# untitled.net
KiCad netlist of a schematic drawn in EAGLE
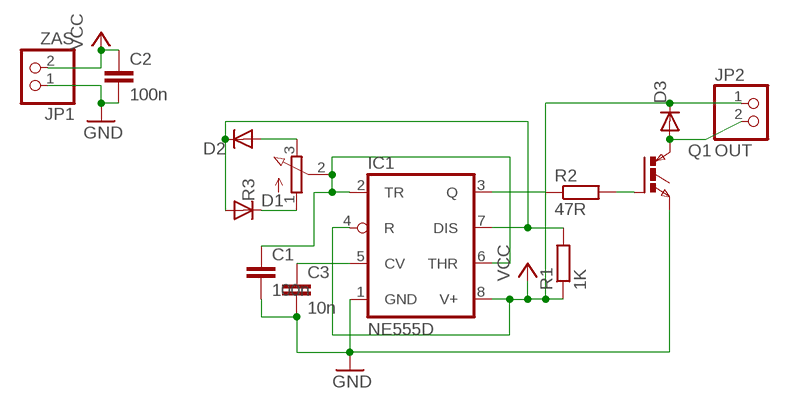
[diagram p0: schematic, sheet 1]

(export (version "E")
  (design (tool "Eeschema 10.0.6"))
  (components
    (comp (ref "C1")
      (value "100n")
      (footprint "eagle-import:C1206")
      (libsource (lib "eagle-import") (part "C-EUC1206"))
    )
    (comp (ref "C2")
      (value "100n")
      (footprint "eagle-import:C1206")
      (libsource (lib "eagle-import") (part "C-EUC1206"))
    )
    (comp (ref "C3")
      (value "10n")
      (footprint "eagle-import:C1206")
      (libsource (lib "eagle-import") (part "C-EUC1206"))
    )
    (comp (ref "D1")
      (value "DIODE-MINIMELF")
      (footprint "eagle-import:MINIMELF")
      (libsource (lib "eagle-import") (part "DIODE-MINIMELF"))
    )
    (comp (ref "D2")
      (value "DIODE-MINIMELF")
      (footprint "eagle-import:MINIMELF")
      (libsource (lib "eagle-import") (part "DIODE-MINIMELF"))
    )
    (comp (ref "D3")
      (value "DIODE-MINIMELF")
      (footprint "eagle-import:MINIMELF")
      (libsource (lib "eagle-import") (part "DIODE-MINIMELF"))
    )
    (comp (ref "IC1")
      (value "NE555D")
      (footprint "eagle-import:SO08")
      (libsource (lib "eagle-import") (part "555DNE"))
    )
    (comp (ref "JP1")
      (value "ZAS")
      (footprint "eagle-import:1X02")
      (libsource (lib "eagle-import") (part "PINHD-1X2"))
    )
    (comp (ref "JP2")
      (value "OUT")
      (footprint "eagle-import:1X02")
      (libsource (lib "eagle-import") (part "PINHD-1X2"))
    )
    (comp (ref "Q1")
      (value "IGBTTO252_STM")
      (footprint "eagle-import:TO252_STM")
      (libsource (lib "eagle-import") (part "IGBTTO252_STM"))
    )
    (comp (ref "R1")
      (value "1K")
      (footprint "eagle-import:R1206")
      (libsource (lib "eagle-import") (part "R-EU_R1206"))
    )
    (comp (ref "R2")
      (value "47R")
      (footprint "eagle-import:R1206")
      (libsource (lib "eagle-import") (part "R-EU_R1206"))
    )
    (comp (ref "R3")
      (value "3RP/1610N")
      (footprint "eagle-import:3RP_1610N")
      (libsource (lib "eagle-import") (part "3RP/1610N"))
    )
  )
  (nets
    (net (code "1") (name "GND") (class "Default")
      (node (ref "C1") (pin "2") (pinfunction "2_2") (pintype "passive"))
      (node (ref "C2") (pin "2") (pinfunction "2_2") (pintype "passive"))
      (node (ref "C3") (pin "2") (pinfunction "2_2") (pintype "passive"))
      (node (ref "IC1") (pin "1") (pinfunction "GND_1") (pintype "power_in"))
      (node (ref "JP1") (pin "1") (pinfunction "1_1") (pintype "passive"))
      (node (ref "Q1") (pin "3") (pinfunction "E_3") (pintype "passive"))
    )
    (net (code "2") (name "Net-(IC1-CV)") (class "Default")
      (node (ref "C3") (pin "1") (pinfunction "1_1") (pintype "passive"))
      (node (ref "IC1") (pin "5") (pinfunction "CV_5") (pintype "input"))
    )
    (net (code "3") (name "Net-(IC1-DIS)") (class "Default")
      (node (ref "D1") (pin "A") (pinfunction "A_A") (pintype "passive"))
      (node (ref "D2") (pin "C") (pinfunction "C_C") (pintype "passive"))
      (node (ref "IC1") (pin "7") (pinfunction "DIS_7") (pintype "input"))
      (node (ref "R1") (pin "2") (pinfunction "2_2") (pintype "passive"))
    )
    (net (code "4") (name "Net-(IC1-Q)") (class "Default")
      (node (ref "IC1") (pin "3") (pinfunction "Q_3") (pintype "output"))
      (node (ref "R2") (pin "1") (pinfunction "1_1") (pintype "passive"))
    )
    (net (code "5") (name "Net-(IC1-THR)") (class "Default")
      (node (ref "C1") (pin "1") (pinfunction "1_1") (pintype "passive"))
      (node (ref "IC1") (pin "2") (pinfunction "TR_2") (pintype "input"))
      (node (ref "IC1") (pin "6") (pinfunction "THR_6") (pintype "input"))
      (node (ref "R3") (pin "2") (pinfunction "S_2") (pintype "passive"))
    )
    (net (code "6") (name "Net-(Q1-C)") (class "Default")
      (node (ref "D3") (pin "A") (pinfunction "A_A") (pintype "passive"))
      (node (ref "JP2") (pin "2") (pinfunction "2_2") (pintype "passive"))
      (node (ref "Q1") (pin "2") (pinfunction "C_2") (pintype "passive"))
    )
    (net (code "7") (name "Net-(Q1-G)") (class "Default")
      (node (ref "Q1") (pin "1") (pinfunction "G_1") (pintype "passive"))
      (node (ref "R2") (pin "2") (pinfunction "2_2") (pintype "passive"))
    )
    (net (code "8") (name "Net-(R3-A)") (class "Default")
      (node (ref "D1") (pin "C") (pinfunction "C_C") (pintype "passive"))
      (node (ref "R3") (pin "1") (pinfunction "A_1") (pintype "passive"))
    )
    (net (code "9") (name "Net-(R3-E)") (class "Default")
      (node (ref "D2") (pin "A") (pinfunction "A_A") (pintype "passive"))
      (node (ref "R3") (pin "3") (pinfunction "E_3") (pintype "passive"))
    )
    (net (code "10") (name "VCC") (class "Default")
      (node (ref "C2") (pin "1") (pinfunction "1_1") (pintype "passive"))
      (node (ref "D3") (pin "C") (pinfunction "C_C") (pintype "passive"))
      (node (ref "IC1") (pin "4") (pinfunction "R_4") (pintype "input"))
      (node (ref "IC1") (pin "8") (pinfunction "V+_8") (pintype "power_in"))
      (node (ref "JP1") (pin "2") (pinfunction "2_2") (pintype "passive"))
      (node (ref "JP2") (pin "1") (pinfunction "1_1") (pintype "passive"))
      (node (ref "R1") (pin "1") (pinfunction "1_1") (pintype "passive"))
    )
  )
)
